# power_rev_3_3.net
KiCad netlist of a schematic drawn in EAGLE
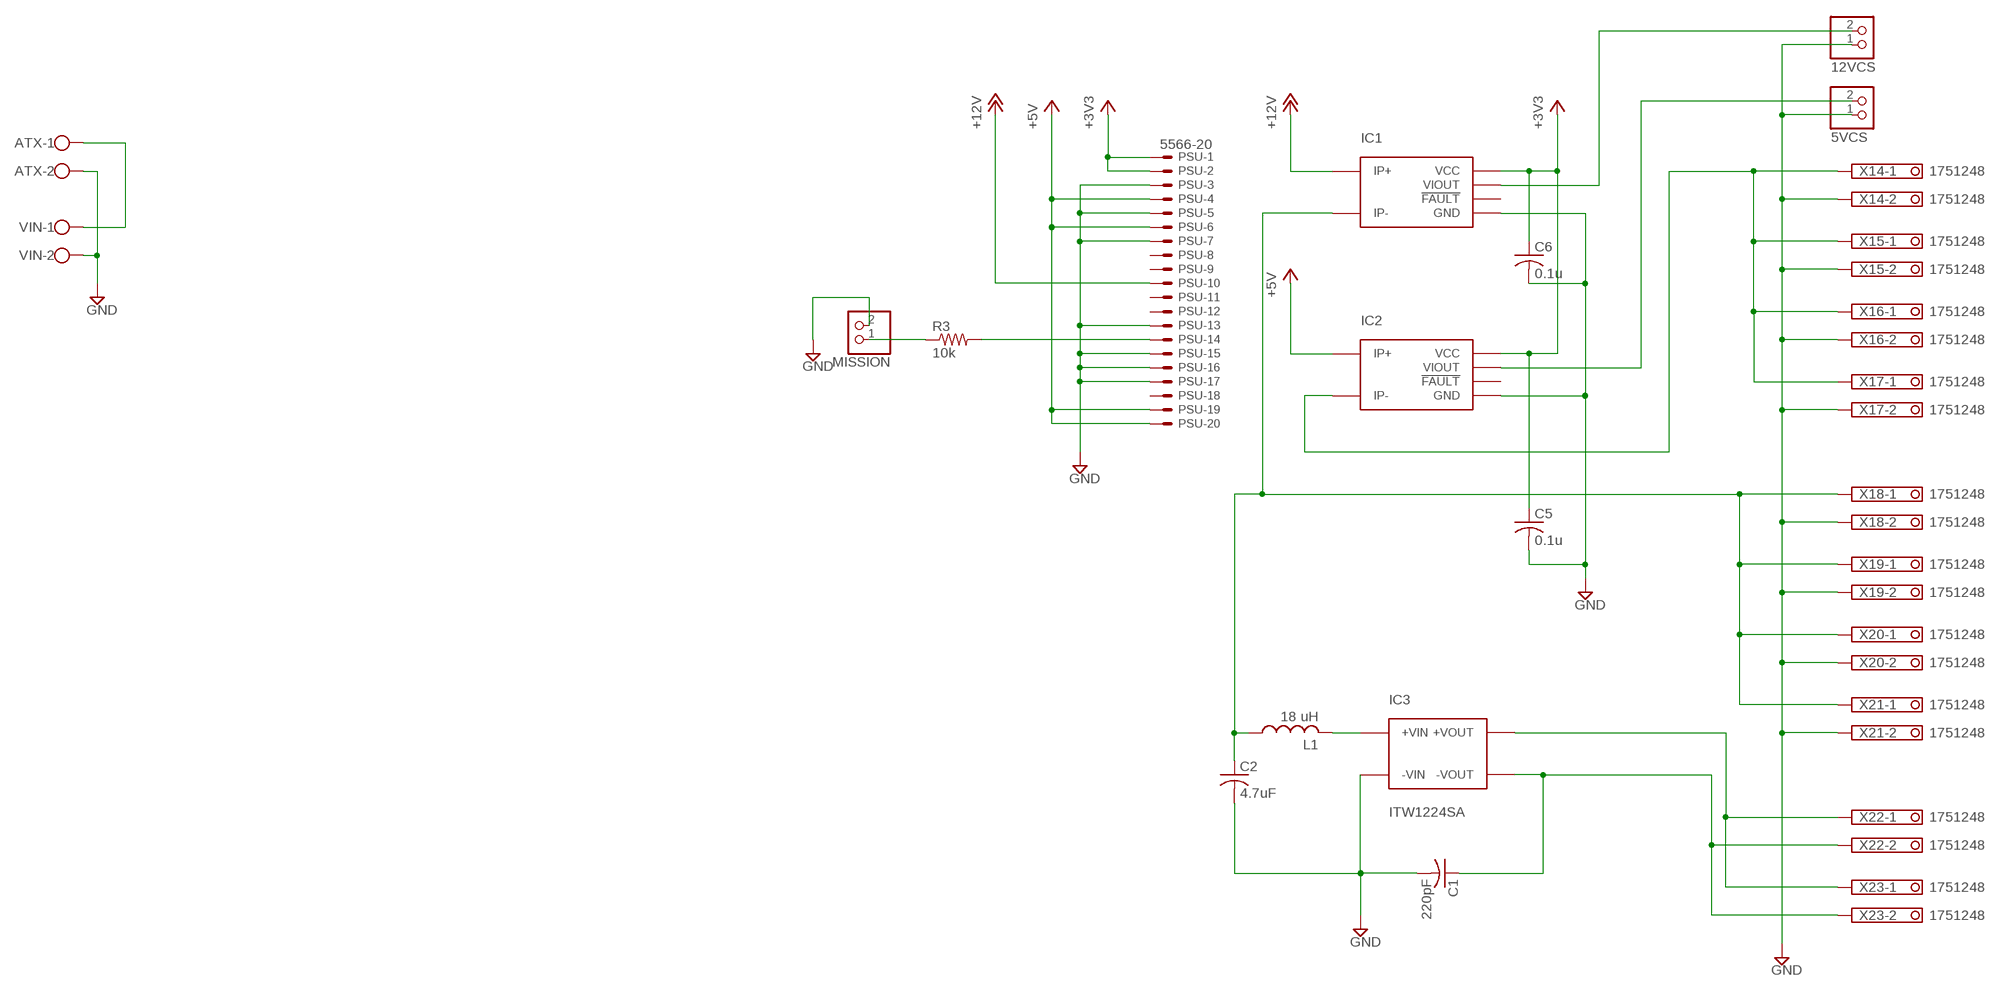
[diagram p0: schematic, sheet 1]

(export (version "E")
  (design (tool "Eeschema 10.0.6"))
  (components
    (comp (ref "5VCS")
      (value "PINHD-1X2")
      (footprint "eagle-import:1X02")
      (libsource (lib "eagle-import") (part "PINHD-1X2"))
    )
    (comp (ref "12VCS")
      (value "PINHD-1X2")
      (footprint "eagle-import:1X02")
      (libsource (lib "eagle-import") (part "PINHD-1X2"))
    )
    (comp (ref "ATX")
      (value "W237-102")
      (footprint "eagle-import:W237-102")
      (fields (field (name "MPN") "237-102"))
      (libsource (lib "eagle-import") (part "W237-102"))
    )
    (comp (ref "C1")
      (value "220pF")
      (footprint "eagle-import:C1206")
      (libsource (lib "eagle-import") (part "resistor_C-USC1206"))
    )
    (comp (ref "C2")
      (value "4.7uF")
      (footprint "eagle-import:C1206")
      (libsource (lib "eagle-import") (part "resistor_C-USC1206"))
    )
    (comp (ref "C5")
      (value "0.1u")
      (footprint "eagle-import:C0805")
      (libsource (lib "eagle-import") (part "C-USC0805"))
    )
    (comp (ref "C6")
      (value "0.1u")
      (footprint "eagle-import:C0805")
      (libsource (lib "eagle-import") (part "C-USC0805"))
    )
    (comp (ref "IC1")
      (value "ACS711")
      (footprint "eagle-import:12-WFQFN")
      (libsource (lib "eagle-import") (part "ACS711"))
    )
    (comp (ref "IC2")
      (value "ACS711")
      (footprint "eagle-import:12-WFQFN")
      (libsource (lib "eagle-import") (part "ACS711"))
    )
    (comp (ref "IC3")
      (value "ITW1224SA")
      (footprint "eagle-import:6-SIP")
      (libsource (lib "eagle-import") (part "ITW1224SA"))
    )
    (comp (ref "L1")
      (value "18 uH")
      (footprint "eagle-import:L2825P")
      (libsource (lib "eagle-import") (part "L-USL2825P"))
    )
    (comp (ref "MISSION")
      (value "PINHD-1X2")
      (footprint "eagle-import:1X02")
      (libsource (lib "eagle-import") (part "PINHD-1X2"))
    )
    (comp (ref "PSU")
      (value "5566-20")
      (footprint "eagle-import:5566-20")
      (libsource (lib "eagle-import") (part "5566-20"))
    )
    (comp (ref "R3")
      (value "10k")
      (footprint "eagle-import:R0805")
      (libsource (lib "eagle-import") (part "R-US_R0805"))
    )
    (comp (ref "VIN")
      (value "W237-102")
      (footprint "eagle-import:W237-102")
      (fields (field (name "MPN") "237-102"))
      (libsource (lib "eagle-import") (part "W237-102"))
    )
    (comp (ref "X14")
      (value "1751248")
      (footprint "eagle-import:1751248")
      (libsource (lib "eagle-import") (part "1751248"))
    )
    (comp (ref "X15")
      (value "1751248")
      (footprint "eagle-import:1751248")
      (libsource (lib "eagle-import") (part "1751248"))
    )
    (comp (ref "X16")
      (value "1751248")
      (footprint "eagle-import:1751248")
      (libsource (lib "eagle-import") (part "1751248"))
    )
    (comp (ref "X17")
      (value "1751248")
      (footprint "eagle-import:1751248")
      (libsource (lib "eagle-import") (part "1751248"))
    )
    (comp (ref "X18")
      (value "1751248")
      (footprint "eagle-import:1751248")
      (libsource (lib "eagle-import") (part "1751248"))
    )
    (comp (ref "X19")
      (value "1751248")
      (footprint "eagle-import:1751248")
      (libsource (lib "eagle-import") (part "1751248"))
    )
    (comp (ref "X20")
      (value "1751248")
      (footprint "eagle-import:1751248")
      (libsource (lib "eagle-import") (part "1751248"))
    )
    (comp (ref "X21")
      (value "1751248")
      (footprint "eagle-import:1751248")
      (libsource (lib "eagle-import") (part "1751248"))
    )
    (comp (ref "X22")
      (value "1751248")
      (footprint "eagle-import:1751248")
      (libsource (lib "eagle-import") (part "1751248"))
    )
    (comp (ref "X23")
      (value "1751248")
      (footprint "eagle-import:1751248")
      (libsource (lib "eagle-import") (part "1751248"))
    )
  )
  (nets
    (net (code "1") (name "+3V3") (class "Default")
      (node (ref "C5") (pin "1") (pinfunction "1_1") (pintype "passive"))
      (node (ref "C6") (pin "1") (pinfunction "1_1") (pintype "passive"))
      (node (ref "IC1") (pin "P$10") (pinfunction "VCC_P$10") (pintype "bidirectional"))
      (node (ref "IC2") (pin "P$10") (pinfunction "VCC_P$10") (pintype "bidirectional"))
      (node (ref "PSU") (pin "1") (pinfunction "S_1") (pintype "passive"))
      (node (ref "PSU") (pin "2") (pinfunction "S_2") (pintype "passive"))
    )
    (net (code "2") (name "+5V") (class "Default")
      (node (ref "IC2") (pin "P$1") (pinfunction "IP+_P$1") (pintype "bidirectional"))
      (node (ref "PSU") (pin "19") (pinfunction "S_19") (pintype "passive"))
      (node (ref "PSU") (pin "20") (pinfunction "S_20") (pintype "passive"))
      (node (ref "PSU") (pin "4") (pinfunction "S_4") (pintype "passive"))
      (node (ref "PSU") (pin "6") (pinfunction "S_6") (pintype "passive"))
    )
    (net (code "3") (name "+12V") (class "Default")
      (node (ref "IC1") (pin "P$1") (pinfunction "IP+_P$1") (pintype "bidirectional"))
      (node (ref "PSU") (pin "10") (pinfunction "S_10") (pintype "passive"))
    )
    (net (code "4") (name "GND") (class "Default")
      (node (ref "12VCS") (pin "1") (pinfunction "1_1") (pintype "passive"))
      (node (ref "5VCS") (pin "1") (pinfunction "1_1") (pintype "passive"))
      (node (ref "ATX") (pin "2") (pinfunction "KL_2") (pintype "passive"))
      (node (ref "C1") (pin "2") (pinfunction "2_2") (pintype "passive"))
      (node (ref "C2") (pin "2") (pinfunction "2_2") (pintype "passive"))
      (node (ref "C5") (pin "2") (pinfunction "2_2") (pintype "passive"))
      (node (ref "C6") (pin "2") (pinfunction "2_2") (pintype "passive"))
      (node (ref "IC1") (pin "P$3") (pinfunction "GND_P$3") (pintype "bidirectional"))
      (node (ref "IC2") (pin "P$3") (pinfunction "GND_P$3") (pintype "bidirectional"))
      (node (ref "IC3") (pin "P$1") (pinfunction "-VIN_P$1") (pintype "bidirectional"))
      (node (ref "MISSION") (pin "2") (pinfunction "2_2") (pintype "passive"))
      (node (ref "PSU") (pin "13") (pinfunction "S_13") (pintype "passive"))
      (node (ref "PSU") (pin "15") (pinfunction "S_15") (pintype "passive"))
      (node (ref "PSU") (pin "16") (pinfunction "S_16") (pintype "passive"))
      (node (ref "PSU") (pin "17") (pinfunction "S_17") (pintype "passive"))
      (node (ref "PSU") (pin "3") (pinfunction "S_3") (pintype "passive"))
      (node (ref "PSU") (pin "5") (pinfunction "S_5") (pintype "passive"))
      (node (ref "PSU") (pin "7") (pinfunction "S_7") (pintype "passive"))
      (node (ref "VIN") (pin "2") (pinfunction "KL_2") (pintype "passive"))
      (node (ref "X14") (pin "2") (pinfunction "K_2") (pintype "passive"))
      (node (ref "X15") (pin "2") (pinfunction "K_2") (pintype "passive"))
      (node (ref "X16") (pin "2") (pinfunction "K_2") (pintype "passive"))
      (node (ref "X17") (pin "2") (pinfunction "K_2") (pintype "passive"))
      (node (ref "X18") (pin "2") (pinfunction "K_2") (pintype "passive"))
      (node (ref "X19") (pin "2") (pinfunction "K_2") (pintype "passive"))
      (node (ref "X20") (pin "2") (pinfunction "K_2") (pintype "passive"))
      (node (ref "X21") (pin "2") (pinfunction "K_2") (pintype "passive"))
    )
    (net (code "5") (name "Net-(ATXA-KL)") (class "Default")
      (node (ref "ATX") (pin "1") (pinfunction "KL_1") (pintype "passive"))
      (node (ref "VIN") (pin "1") (pinfunction "KL_1") (pintype "passive"))
    )
    (net (code "6") (name "Net-(IC1-IP-)") (class "Default")
      (node (ref "C2") (pin "1") (pinfunction "1_1") (pintype "passive"))
      (node (ref "IC1") (pin "P$2") (pinfunction "IP-_P$2") (pintype "bidirectional"))
      (node (ref "L1") (pin "1") (pinfunction "1_1") (pintype "passive"))
      (node (ref "X18") (pin "1") (pinfunction "K_1") (pintype "passive"))
      (node (ref "X19") (pin "1") (pinfunction "K_1") (pintype "passive"))
      (node (ref "X20") (pin "1") (pinfunction "K_1") (pintype "passive"))
      (node (ref "X21") (pin "1") (pinfunction "K_1") (pintype "passive"))
    )
    (net (code "7") (name "Net-(IC1-VIOUT)") (class "Default")
      (node (ref "12VCS") (pin "2") (pinfunction "2_2") (pintype "passive"))
      (node (ref "IC1") (pin "P$9") (pinfunction "VIOUT_P$9") (pintype "bidirectional"))
    )
    (net (code "8") (name "Net-(IC2-IP-)") (class "Default")
      (node (ref "IC2") (pin "P$2") (pinfunction "IP-_P$2") (pintype "bidirectional"))
      (node (ref "X14") (pin "1") (pinfunction "K_1") (pintype "passive"))
      (node (ref "X15") (pin "1") (pinfunction "K_1") (pintype "passive"))
      (node (ref "X16") (pin "1") (pinfunction "K_1") (pintype "passive"))
      (node (ref "X17") (pin "1") (pinfunction "K_1") (pintype "passive"))
    )
    (net (code "9") (name "Net-(IC2-VIOUT)") (class "Default")
      (node (ref "5VCS") (pin "2") (pinfunction "2_2") (pintype "passive"))
      (node (ref "IC2") (pin "P$9") (pinfunction "VIOUT_P$9") (pintype "bidirectional"))
    )
    (net (code "10") (name "Net-(IC3-+VIN)") (class "Default")
      (node (ref "IC3") (pin "P$2") (pinfunction "+VIN_P$2") (pintype "bidirectional"))
      (node (ref "L1") (pin "2") (pinfunction "2_2") (pintype "passive"))
    )
    (net (code "11") (name "Net-(IC3-+VOUT)") (class "Default")
      (node (ref "IC3") (pin "P$3") (pinfunction "+VOUT_P$3") (pintype "bidirectional"))
      (node (ref "X22") (pin "1") (pinfunction "K_1") (pintype "passive"))
      (node (ref "X23") (pin "1") (pinfunction "K_1") (pintype "passive"))
    )
    (net (code "12") (name "Net-(IC3--VOUT)") (class "Default")
      (node (ref "C1") (pin "1") (pinfunction "1_1") (pintype "passive"))
      (node (ref "IC3") (pin "P$5") (pinfunction "-VOUT_P$5") (pintype "bidirectional"))
      (node (ref "X22") (pin "2") (pinfunction "K_2") (pintype "passive"))
      (node (ref "X23") (pin "2") (pinfunction "K_2") (pintype "passive"))
    )
    (net (code "13") (name "Net-(MISSION-Pad1)") (class "Default")
      (node (ref "MISSION") (pin "1") (pinfunction "1_1") (pintype "passive"))
      (node (ref "R3") (pin "1") (pinfunction "1_1") (pintype "passive"))
    )
    (net (code "14") (name "Net-(PSUF-S)") (class "Default")
      (node (ref "PSU") (pin "14") (pinfunction "S_14") (pintype "passive"))
      (node (ref "R3") (pin "2") (pinfunction "2_2") (pintype "passive"))
    )
    (net (code "15") (name "unconnected-(IC1-~{FAULT}-PadP$4)") (class "Default")
      (node (ref "IC1") (pin "P$4") (pinfunction "~{FAULT}_P$4") (pintype "bidirectional"))
    )
    (net (code "16") (name "unconnected-(IC2-~{FAULT}-PadP$4)") (class "Default")
      (node (ref "IC2") (pin "P$4") (pinfunction "~{FAULT}_P$4") (pintype "bidirectional"))
    )
    (net (code "17") (name "unconnected-(PSUC-S-Pad11)") (class "Default")
      (node (ref "PSU") (pin "11") (pinfunction "S_11") (pintype "passive"))
    )
    (net (code "18") (name "unconnected-(PSUD-S-Pad12)") (class "Default")
      (node (ref "PSU") (pin "12") (pinfunction "S_12") (pintype "passive"))
    )
    (net (code "19") (name "unconnected-(PSUJ-S-Pad18)") (class "Default")
      (node (ref "PSU") (pin "18") (pinfunction "S_18") (pintype "passive"))
    )
    (net (code "20") (name "unconnected-(PSUS-S-Pad8)") (class "Default")
      (node (ref "PSU") (pin "8") (pinfunction "S_8") (pintype "passive"))
    )
    (net (code "21") (name "unconnected-(PSUT-S-Pad9)") (class "Default")
      (node (ref "PSU") (pin "9") (pinfunction "S_9") (pintype "passive"))
    )
  )
)
